# provisorio_5.net
KiCad netlist of a schematic drawn in EAGLE
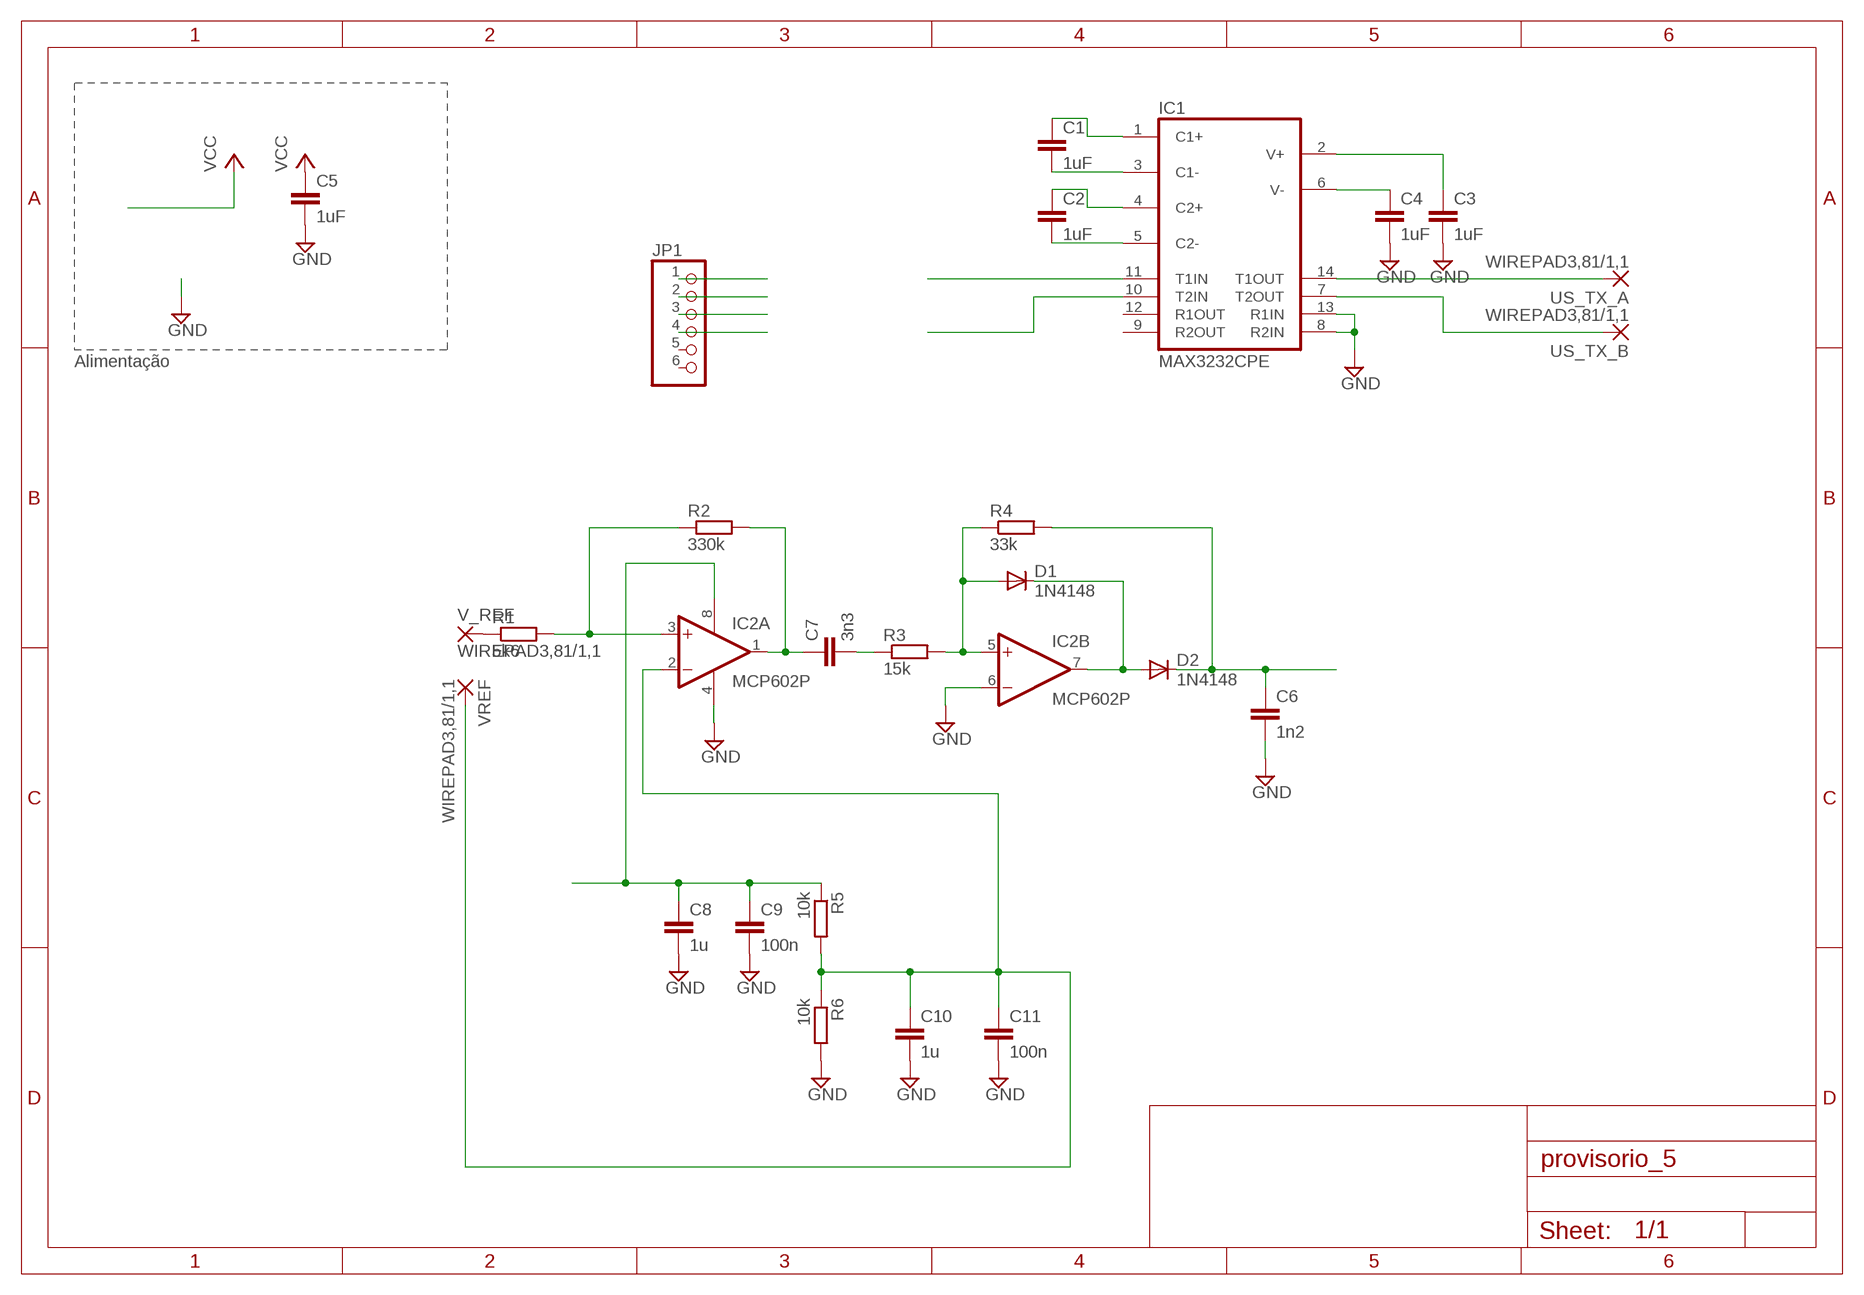
[diagram p0: schematic, sheet 1]

(export (version "E")
  (design (tool "Eeschema 10.0.6"))
  (components
    (comp (ref "C1")
      (value "1uF")
      (footprint "eagle-import:C1206K")
      (libsource (lib "eagle-import") (part "C-EUC1206K"))
    )
    (comp (ref "C2")
      (value "1uF")
      (footprint "eagle-import:C1206K")
      (libsource (lib "eagle-import") (part "C-EUC1206K"))
    )
    (comp (ref "C3")
      (value "1uF")
      (footprint "eagle-import:C1206K")
      (libsource (lib "eagle-import") (part "C-EUC1206K"))
    )
    (comp (ref "C4")
      (value "1uF")
      (footprint "eagle-import:C1206K")
      (libsource (lib "eagle-import") (part "C-EUC1206K"))
    )
    (comp (ref "C5")
      (value "1uF")
      (footprint "eagle-import:C1206K")
      (libsource (lib "eagle-import") (part "C-EUC1206K"))
    )
    (comp (ref "C6")
      (value "1n2")
      (footprint "eagle-import:C1206K")
      (libsource (lib "eagle-import") (part "C-EUC1206K"))
    )
    (comp (ref "C7")
      (value "3n3")
      (footprint "eagle-import:C1206K")
      (libsource (lib "eagle-import") (part "C-EUC1206K"))
    )
    (comp (ref "C8")
      (value "1u")
      (footprint "eagle-import:C1206K")
      (libsource (lib "eagle-import") (part "C-EUC1206K"))
    )
    (comp (ref "C9")
      (value "100n")
      (footprint "eagle-import:C1206K")
      (libsource (lib "eagle-import") (part "C-EUC1206K"))
    )
    (comp (ref "C10")
      (value "1u")
      (footprint "eagle-import:C1206K")
      (libsource (lib "eagle-import") (part "C-EUC1206K"))
    )
    (comp (ref "C11")
      (value "100n")
      (footprint "eagle-import:C1206K")
      (libsource (lib "eagle-import") (part "C-EUC1206K"))
    )
    (comp (ref "D1")
      (value "1N4148")
      (footprint "eagle-import:SOD123")
      (libsource (lib "eagle-import") (part "DIODE-SOD123"))
    )
    (comp (ref "D2")
      (value "1N4148")
      (footprint "eagle-import:SOD123")
      (libsource (lib "eagle-import") (part "DIODE-SOD123"))
    )
    (comp (ref "IC1")
      (value "MAX3232CPE")
      (footprint "eagle-import:DIL16")
      (fields (field (name "MF") "MAXIM") (field (name "MPN") "MAX3232CPE+"))
      (libsource (lib "eagle-import") (part "MAX3232PEC"))
    )
    (comp (ref "IC2")
      (value "MCP602P")
      (footprint "eagle-import:DIL08")
      (libsource (lib "eagle-import") (part "MCP602P"))
    )
    (comp (ref "JP1")
      (value "PINHD-1X6")
      (footprint "eagle-import:1X06")
      (libsource (lib "eagle-import") (part "PINHD-1X6"))
    )
    (comp (ref "R1")
      (value "5k6")
      (footprint "eagle-import:R1206")
      (libsource (lib "eagle-import") (part "R-EU_R1206"))
    )
    (comp (ref "R2")
      (value "330k")
      (footprint "eagle-import:R1206")
      (libsource (lib "eagle-import") (part "R-EU_R1206"))
    )
    (comp (ref "R3")
      (value "15k")
      (footprint "eagle-import:R1206")
      (libsource (lib "eagle-import") (part "R-EU_R1206"))
    )
    (comp (ref "R4")
      (value "33k")
      (footprint "eagle-import:R1206")
      (libsource (lib "eagle-import") (part "R-EU_R1206"))
    )
    (comp (ref "R5")
      (value "10k")
      (footprint "eagle-import:R1206")
      (libsource (lib "eagle-import") (part "R-EU_R1206"))
    )
    (comp (ref "R6")
      (value "10k")
      (footprint "eagle-import:R1206")
      (libsource (lib "eagle-import") (part "R-EU_R1206"))
    )
    (comp (ref "US_TX_A")
      (value "WIREPAD3,81/1,1")
      (footprint "eagle-import:3,81_1,1")
      (libsource (lib "eagle-import") (part "WIREPAD3,81/1,1"))
    )
    (comp (ref "US_TX_B")
      (value "WIREPAD3,81/1,1")
      (footprint "eagle-import:3,81_1,1")
      (libsource (lib "eagle-import") (part "WIREPAD3,81/1,1"))
    )
    (comp (ref "VREF")
      (value "WIREPAD3,81/1,1")
      (footprint "eagle-import:3,81_1,1")
      (libsource (lib "eagle-import") (part "WIREPAD3,81/1,1"))
    )
    (comp (ref "V_REF")
      (value "WIREPAD3,81/1,1")
      (footprint "eagle-import:3,81_1,1")
      (libsource (lib "eagle-import") (part "WIREPAD3,81/1,1"))
    )
  )
  (nets
    (net (code "1") (name "/DIGI1") (class "Default")
      (node (ref "C6") (pin "1") (pinfunction "1_1") (pintype "passive"))
      (node (ref "D2") (pin "C") (pinfunction "C_C") (pintype "passive"))
      (node (ref "IC1") (pin "11") (pinfunction "T1IN_11") (pintype "input"))
      (node (ref "JP1") (pin "2") (pinfunction "2_2") (pintype "passive"))
      (node (ref "R4") (pin "2") (pinfunction "2_2") (pintype "passive"))
    )
    (net (code "2") (name "/DIGI2") (class "Default")
      (node (ref "IC1") (pin "10") (pinfunction "T2IN_10") (pintype "input"))
      (node (ref "JP1") (pin "1") (pinfunction "1_1") (pintype "passive"))
    )
    (net (code "3") (name "GND") (class "Default")
      (node (ref "C10") (pin "2") (pinfunction "2_2") (pintype "passive"))
      (node (ref "C11") (pin "2") (pinfunction "2_2") (pintype "passive"))
      (node (ref "C3") (pin "2") (pinfunction "2_2") (pintype "passive"))
      (node (ref "C4") (pin "2") (pinfunction "2_2") (pintype "passive"))
      (node (ref "C5") (pin "2") (pinfunction "2_2") (pintype "passive"))
      (node (ref "C6") (pin "2") (pinfunction "2_2") (pintype "passive"))
      (node (ref "C8") (pin "2") (pinfunction "2_2") (pintype "passive"))
      (node (ref "C9") (pin "2") (pinfunction "2_2") (pintype "passive"))
      (node (ref "IC1") (pin "13") (pinfunction "R1IN_13") (pintype "input"))
      (node (ref "IC1") (pin "8") (pinfunction "R2IN_8") (pintype "input"))
      (node (ref "IC2") (pin "4") (pinfunction "V-_4") (pintype "power_in"))
      (node (ref "IC2") (pin "6") (pinfunction "-IN_6") (pintype "input"))
      (node (ref "JP1") (pin "3") (pinfunction "3_3") (pintype "passive"))
      (node (ref "R6") (pin "2") (pinfunction "2_2") (pintype "passive"))
    )
    (net (code "4") (name "Net-(C7-Pad2)") (class "Default")
      (node (ref "C7") (pin "2") (pinfunction "2_2") (pintype "passive"))
      (node (ref "R3") (pin "1") (pinfunction "1_1") (pintype "passive"))
    )
    (net (code "5") (name "Net-(IC1A-C1+)") (class "Default")
      (node (ref "C1") (pin "1") (pinfunction "1_1") (pintype "passive"))
      (node (ref "IC1") (pin "1") (pinfunction "C1+_1") (pintype "bidirectional"))
    )
    (net (code "6") (name "Net-(IC1A-C1-)") (class "Default")
      (node (ref "C1") (pin "2") (pinfunction "2_2") (pintype "passive"))
      (node (ref "IC1") (pin "3") (pinfunction "C1-_3") (pintype "bidirectional"))
    )
    (net (code "7") (name "Net-(IC1A-C2+)") (class "Default")
      (node (ref "C2") (pin "1") (pinfunction "1_1") (pintype "passive"))
      (node (ref "IC1") (pin "4") (pinfunction "C2+_4") (pintype "bidirectional"))
    )
    (net (code "8") (name "Net-(IC1A-C2-)") (class "Default")
      (node (ref "C2") (pin "2") (pinfunction "2_2") (pintype "passive"))
      (node (ref "IC1") (pin "5") (pinfunction "C2-_5") (pintype "bidirectional"))
    )
    (net (code "9") (name "Net-(IC1A-T1OUT)") (class "Default")
      (node (ref "IC1") (pin "14") (pinfunction "T1OUT_14") (pintype "output"))
      (node (ref "US_TX_A") (pin "1") (pinfunction "P_1") (pintype "passive"))
    )
    (net (code "10") (name "Net-(IC1A-T2OUT)") (class "Default")
      (node (ref "IC1") (pin "7") (pinfunction "T2OUT_7") (pintype "output"))
      (node (ref "US_TX_B") (pin "1") (pinfunction "P_1") (pintype "passive"))
    )
    (net (code "11") (name "Net-(IC1A-V+)") (class "Default")
      (node (ref "C3") (pin "1") (pinfunction "1_1") (pintype "passive"))
      (node (ref "IC1") (pin "2") (pinfunction "V+_2") (pintype "bidirectional"))
    )
    (net (code "12") (name "Net-(IC1A-V-)") (class "Default")
      (node (ref "C4") (pin "1") (pinfunction "1_1") (pintype "passive"))
      (node (ref "IC1") (pin "6") (pinfunction "V-_6") (pintype "bidirectional"))
    )
    (net (code "13") (name "Net-(IC2A-+IN)") (class "Default")
      (node (ref "IC2") (pin "3") (pinfunction "+IN_3") (pintype "input"))
      (node (ref "R1") (pin "2") (pinfunction "2_2") (pintype "passive"))
      (node (ref "R2") (pin "1") (pinfunction "1_1") (pintype "passive"))
    )
    (net (code "14") (name "Net-(IC2A--IN)") (class "Default")
      (node (ref "C10") (pin "1") (pinfunction "1_1") (pintype "passive"))
      (node (ref "C11") (pin "1") (pinfunction "1_1") (pintype "passive"))
      (node (ref "IC2") (pin "2") (pinfunction "-IN_2") (pintype "input"))
      (node (ref "R5") (pin "2") (pinfunction "2_2") (pintype "passive"))
      (node (ref "R6") (pin "1") (pinfunction "1_1") (pintype "passive"))
      (node (ref "VREF") (pin "1") (pinfunction "P_1") (pintype "passive"))
    )
    (net (code "15") (name "Net-(IC2A-OUT)") (class "Default")
      (node (ref "C7") (pin "1") (pinfunction "1_1") (pintype "passive"))
      (node (ref "IC2") (pin "1") (pinfunction "OUT_1") (pintype "output"))
      (node (ref "R2") (pin "2") (pinfunction "2_2") (pintype "passive"))
    )
    (net (code "16") (name "Net-(IC2B-+IN)") (class "Default")
      (node (ref "D1") (pin "A") (pinfunction "A_A") (pintype "passive"))
      (node (ref "IC2") (pin "5") (pinfunction "+IN_5") (pintype "input"))
      (node (ref "R3") (pin "2") (pinfunction "2_2") (pintype "passive"))
      (node (ref "R4") (pin "1") (pinfunction "1_1") (pintype "passive"))
    )
    (net (code "17") (name "Net-(IC2B-OUT)") (class "Default")
      (node (ref "D1") (pin "C") (pinfunction "C_C") (pintype "passive"))
      (node (ref "D2") (pin "A") (pinfunction "A_A") (pintype "passive"))
      (node (ref "IC2") (pin "7") (pinfunction "OUT_7") (pintype "output"))
    )
    (net (code "18") (name "Net-(V_REF-P)") (class "Default")
      (node (ref "R1") (pin "1") (pinfunction "1_1") (pintype "passive"))
      (node (ref "V_REF") (pin "1") (pinfunction "P_1") (pintype "passive"))
    )
    (net (code "19") (name "VCC") (class "Default")
      (node (ref "C5") (pin "1") (pinfunction "1_1") (pintype "passive"))
      (node (ref "C8") (pin "1") (pinfunction "1_1") (pintype "passive"))
      (node (ref "C9") (pin "1") (pinfunction "1_1") (pintype "passive"))
      (node (ref "IC2") (pin "8") (pinfunction "V+_8") (pintype "power_in"))
      (node (ref "JP1") (pin "4") (pinfunction "4_4") (pintype "passive"))
      (node (ref "R5") (pin "1") (pinfunction "1_1") (pintype "passive"))
    )
    (net (code "20") (name "unconnected-(IC1A-R1OUT-Pad12)") (class "Default")
      (node (ref "IC1") (pin "12") (pinfunction "R1OUT_12") (pintype "output"))
    )
    (net (code "21") (name "unconnected-(IC1A-R2OUT-Pad9)") (class "Default")
      (node (ref "IC1") (pin "9") (pinfunction "R2OUT_9") (pintype "output"))
    )
    (net (code "22") (name "unconnected-(JP1-Pad5)") (class "Default")
      (node (ref "JP1") (pin "5") (pinfunction "5_5") (pintype "passive"))
    )
    (net (code "23") (name "unconnected-(JP1-Pad6)") (class "Default")
      (node (ref "JP1") (pin "6") (pinfunction "6_6") (pintype "passive"))
    )
  )
)
